# ADC_PWM_Board_-_Rev_A2.net
KiCad netlist of a schematic drawn in EAGLE
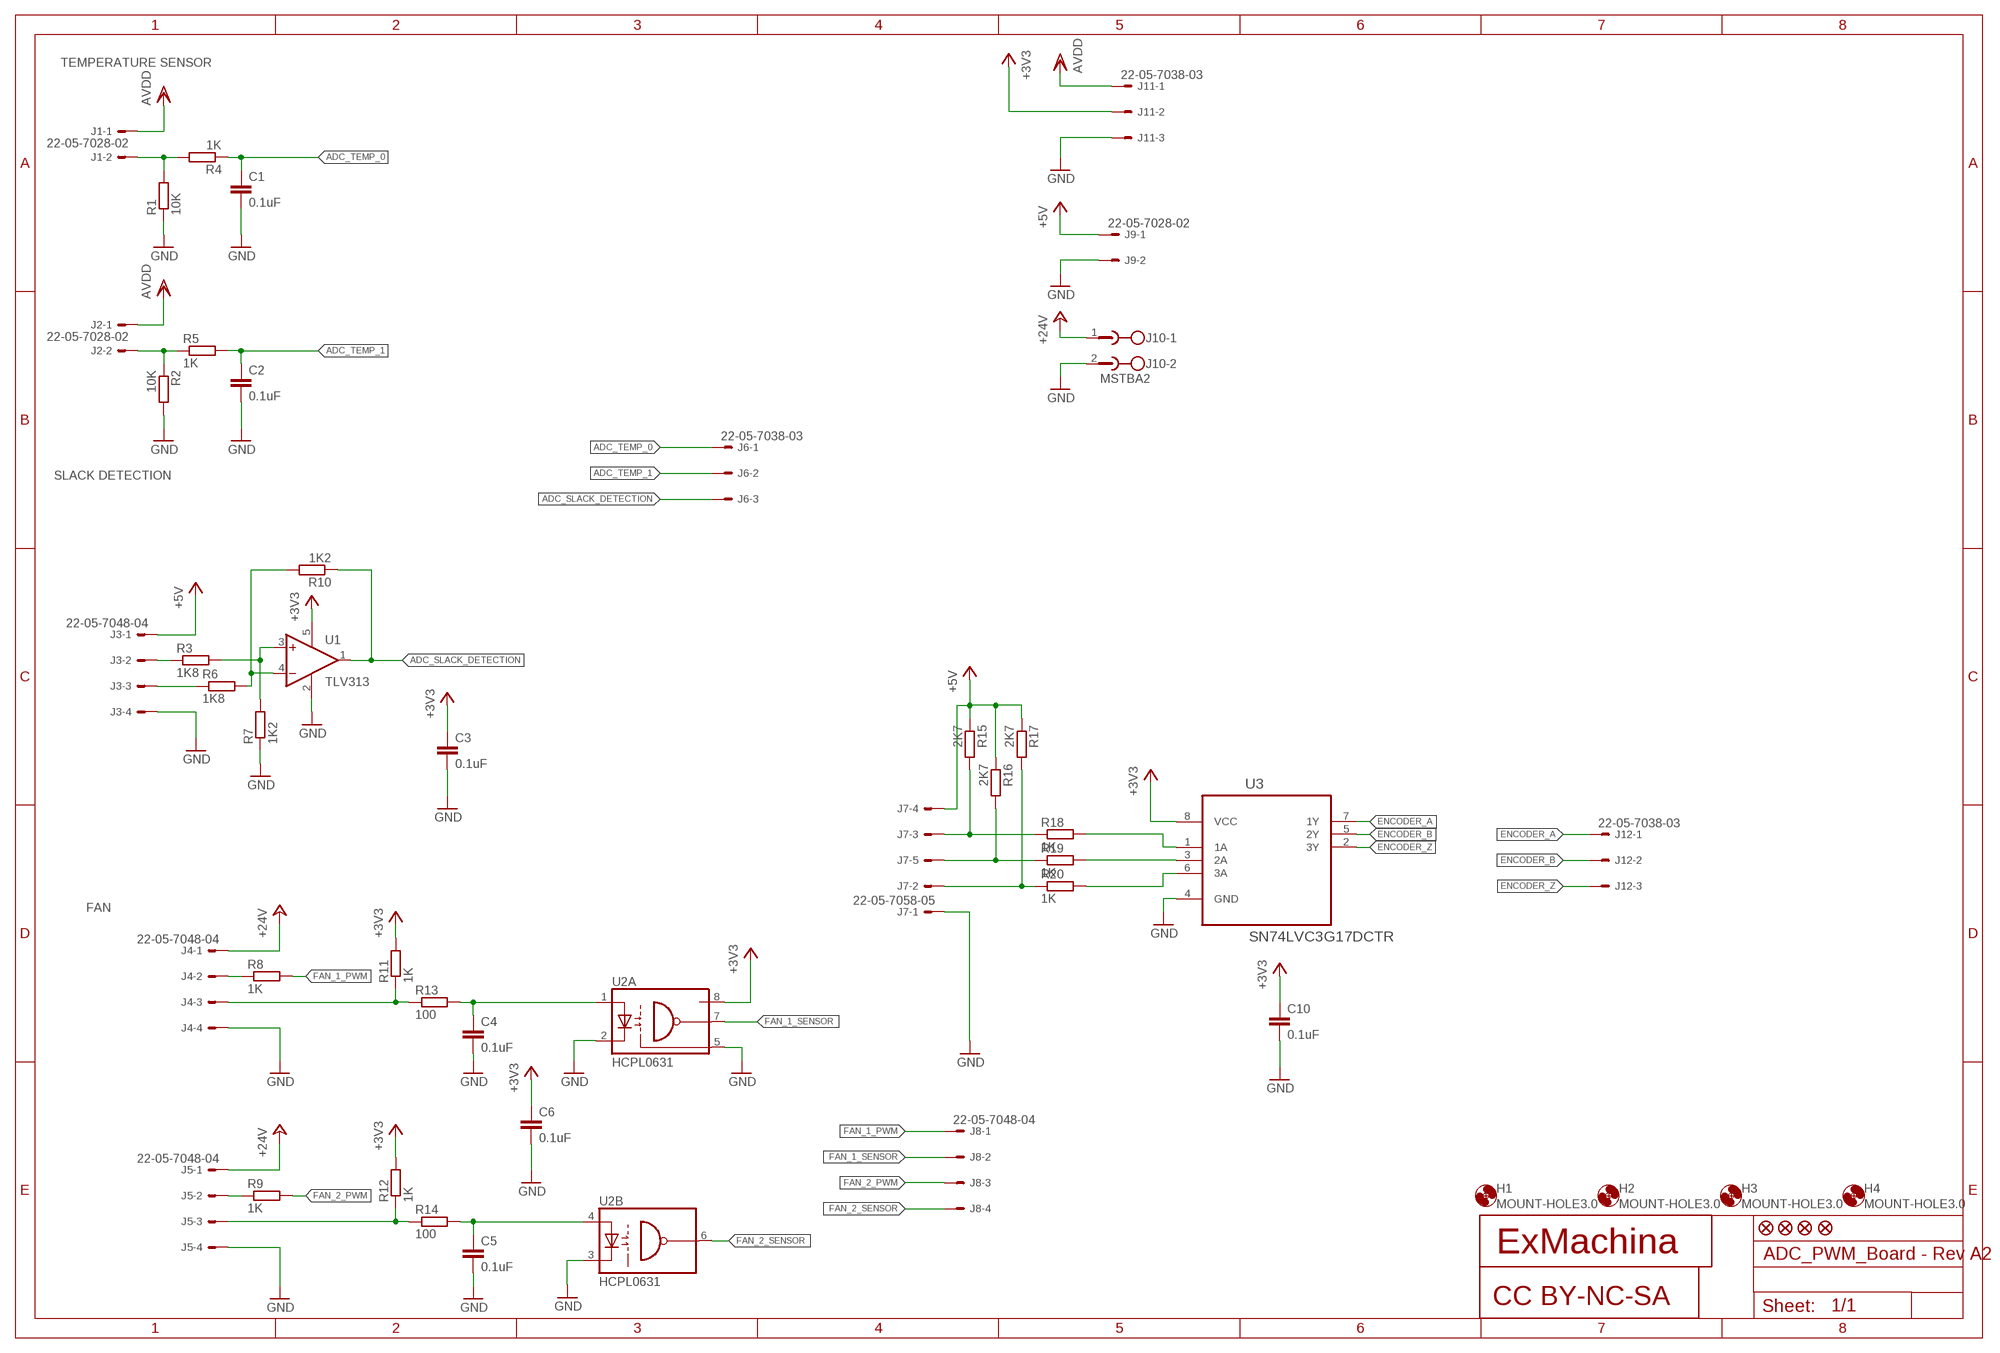
[diagram p0: schematic, sheet 1]

(export (version "E")
  (design (tool "Eeschema 10.0.6"))
  (components
    (comp (ref "C1")
      (value "0.1uF")
      (footprint "eagle-import:C0603")
      (fields (field (name "MPN") "MC0603B104K250CT"))
      (libsource (lib "eagle-import") (part "C-EUC0603"))
    )
    (comp (ref "C2")
      (value "0.1uF")
      (footprint "eagle-import:C0603")
      (fields (field (name "MPN") "MC0603B104K250CT"))
      (libsource (lib "eagle-import") (part "C-EUC0603"))
    )
    (comp (ref "C3")
      (value "0.1uF")
      (footprint "eagle-import:C0603")
      (fields (field (name "MPN") "MC0603B104K250CT"))
      (libsource (lib "eagle-import") (part "C-EUC0603"))
    )
    (comp (ref "C4")
      (value "0.1uF")
      (footprint "eagle-import:C0603")
      (fields (field (name "MPN") "MC0603B104K250CT"))
      (libsource (lib "eagle-import") (part "C-EUC0603"))
    )
    (comp (ref "C5")
      (value "0.1uF")
      (footprint "eagle-import:C0603")
      (fields (field (name "MPN") "MC0603B104K250CT"))
      (libsource (lib "eagle-import") (part "C-EUC0603"))
    )
    (comp (ref "C6")
      (value "0.1uF")
      (footprint "eagle-import:C0603")
      (fields (field (name "MPN") "MC0603B104K250CT"))
      (libsource (lib "eagle-import") (part "C-EUC0603"))
    )
    (comp (ref "C10")
      (value "0.1uF")
      (footprint "eagle-import:C0603")
      (fields (field (name "MPN") "MC0603B104K250CT"))
      (libsource (lib "eagle-import") (part "C-EUC0603"))
    )
    (comp (ref "CC1")
      (value "CC-BY-NC-SA")
      (footprint "eagle-import:CC-BY-NC-SA")
      (libsource (lib "eagle-import") (part "CC-BY-NC-SA"))
    )
    (comp (ref "H1")
      (value "MOUNT-HOLE3.0")
      (footprint "eagle-import:3,0")
      (libsource (lib "eagle-import") (part "MOUNT-HOLE3.0"))
    )
    (comp (ref "H2")
      (value "MOUNT-HOLE3.0")
      (footprint "eagle-import:3,0")
      (libsource (lib "eagle-import") (part "MOUNT-HOLE3.0"))
    )
    (comp (ref "H3")
      (value "MOUNT-HOLE3.0")
      (footprint "eagle-import:3,0")
      (libsource (lib "eagle-import") (part "MOUNT-HOLE3.0"))
    )
    (comp (ref "H4")
      (value "MOUNT-HOLE3.0")
      (footprint "eagle-import:3,0")
      (libsource (lib "eagle-import") (part "MOUNT-HOLE3.0"))
    )
    (comp (ref "J1")
      (value "22-05-7028-02")
      (footprint "eagle-import:7395-02")
      (fields (field (name "MPN") "22-05-7028") (field (name "OC_NEWARK") "25M1728"))
      (libsource (lib "eagle-import") (part "22-?-0205-7028"))
    )
    (comp (ref "J2")
      (value "22-05-7028-02")
      (footprint "eagle-import:7395-02")
      (fields (field (name "MPN") "22-05-7028") (field (name "OC_NEWARK") "25M1728"))
      (libsource (lib "eagle-import") (part "22-?-0205-7028"))
    )
    (comp (ref "J3")
      (value "22-05-7048-04")
      (footprint "eagle-import:7395-04")
      (fields (field (name "MPN") "22-05-7048") (field (name "OC_NEWARK") "26M6363"))
      (libsource (lib "eagle-import") (part "22-?-0405-7048"))
    )
    (comp (ref "J4")
      (value "22-05-7048-04")
      (footprint "eagle-import:7395-04")
      (fields (field (name "MPN") "22-05-7048") (field (name "OC_NEWARK") "26M6363"))
      (libsource (lib "eagle-import") (part "22-?-0405-7048"))
    )
    (comp (ref "J5")
      (value "22-05-7048-04")
      (footprint "eagle-import:7395-04")
      (fields (field (name "MPN") "22-05-7048") (field (name "OC_NEWARK") "26M6363"))
      (libsource (lib "eagle-import") (part "22-?-0405-7048"))
    )
    (comp (ref "J6")
      (value "22-05-7038-03")
      (footprint "eagle-import:7395-03")
      (fields (field (name "MPN") "22-05-7038") (field (name "OC_NEWARK") "26M6362"))
      (libsource (lib "eagle-import") (part "22-?-0305-7038"))
    )
    (comp (ref "J7")
      (value "22-05-7058-05")
      (footprint "eagle-import:7395-05")
      (fields
        (field (name "MF") "MOLEX")
        (field (name "MPN") "22-05-7058")
        (field (name "OC_NEWARK") "55H9619")
      )
      (libsource (lib "eagle-import") (part "22-?-0505-7058"))
    )
    (comp (ref "J8")
      (value "22-05-7048-04")
      (footprint "eagle-import:7395-04")
      (fields (field (name "MPN") "22-05-7048") (field (name "OC_NEWARK") "26M6363"))
      (libsource (lib "eagle-import") (part "22-?-0405-7048"))
    )
    (comp (ref "J9")
      (value "22-05-7028-02")
      (footprint "eagle-import:7395-02")
      (fields (field (name "MPN") "22-05-7028") (field (name "OC_NEWARK") "25M1728"))
      (libsource (lib "eagle-import") (part "22-?-0205-7028"))
    )
    (comp (ref "J10")
      (value "MSTBA2")
      (footprint "eagle-import:MSTBA2")
      (fields (field (name "MF") "FARNELL") (field (name "MPN") "1757242"))
      (libsource (lib "eagle-import") (part "MSTBA2"))
    )
    (comp (ref "J11")
      (value "22-05-7038-03")
      (footprint "eagle-import:7395-03")
      (fields (field (name "MPN") "22-05-7038") (field (name "OC_NEWARK") "26M6362"))
      (libsource (lib "eagle-import") (part "22-?-0305-7038"))
    )
    (comp (ref "J12")
      (value "22-05-7038-03")
      (footprint "eagle-import:7395-03")
      (fields (field (name "MPN") "22-05-7038") (field (name "OC_NEWARK") "26M6362"))
      (libsource (lib "eagle-import") (part "22-?-0305-7038"))
    )
    (comp (ref "JP1")
      (value "FIDUCIAL1X2")
      (footprint "eagle-import:FIDUCIAL-1X2")
      (libsource (lib "eagle-import") (part "FIDUCIAL1X2"))
    )
    (comp (ref "JP2")
      (value "FIDUCIAL1X2")
      (footprint "eagle-import:FIDUCIAL-1X2")
      (libsource (lib "eagle-import") (part "FIDUCIAL1X2"))
    )
    (comp (ref "JP3")
      (value "FIDUCIAL1X2")
      (footprint "eagle-import:FIDUCIAL-1X2")
      (libsource (lib "eagle-import") (part "FIDUCIAL1X2"))
    )
    (comp (ref "JP4")
      (value "FIDUCIAL1X2")
      (footprint "eagle-import:FIDUCIAL-1X2")
      (libsource (lib "eagle-import") (part "FIDUCIAL1X2"))
    )
    (comp (ref "R1")
      (value "10K")
      (footprint "eagle-import:R0603")
      (fields (field (name "MPN") "MCMR06X1002FTL"))
      (libsource (lib "eagle-import") (part "R-EU_R0603"))
    )
    (comp (ref "R2")
      (value "10K")
      (footprint "eagle-import:R0603")
      (fields (field (name "MPN") "MCMR06X1002FTL"))
      (libsource (lib "eagle-import") (part "R-EU_R0603"))
    )
    (comp (ref "R3")
      (value "1K8")
      (footprint "eagle-import:R0603")
      (fields (field (name "MPN") "MCMR06X1801FTL"))
      (libsource (lib "eagle-import") (part "R-EU_R0603"))
    )
    (comp (ref "R4")
      (value "1K")
      (footprint "eagle-import:R0603")
      (fields (field (name "MPN") "MCMR06X1001FTL"))
      (libsource (lib "eagle-import") (part "R-EU_R0603"))
    )
    (comp (ref "R5")
      (value "1K")
      (footprint "eagle-import:R0603")
      (fields (field (name "MPN") "MCMR06X1001FTL"))
      (libsource (lib "eagle-import") (part "R-EU_R0603"))
    )
    (comp (ref "R6")
      (value "1K8")
      (footprint "eagle-import:R0603")
      (fields (field (name "MPN") "MCMR06X1801FTL"))
      (libsource (lib "eagle-import") (part "R-EU_R0603"))
    )
    (comp (ref "R7")
      (value "1K2")
      (footprint "eagle-import:R0603")
      (fields (field (name "MPN") "MCMR06X1201FTL"))
      (libsource (lib "eagle-import") (part "R-EU_R0603"))
    )
    (comp (ref "R8")
      (value "1K")
      (footprint "eagle-import:R0603")
      (fields (field (name "MPN") "MCMR06X1001FTL"))
      (libsource (lib "eagle-import") (part "R-EU_R0603"))
    )
    (comp (ref "R9")
      (value "1K")
      (footprint "eagle-import:R0603")
      (fields (field (name "MPN") "MCMR06X1001FTL"))
      (libsource (lib "eagle-import") (part "R-EU_R0603"))
    )
    (comp (ref "R10")
      (value "1K2")
      (footprint "eagle-import:R0603")
      (fields (field (name "MPN") "MCMR06X1201FTL"))
      (libsource (lib "eagle-import") (part "R-EU_R0603"))
    )
    (comp (ref "R11")
      (value "1K")
      (footprint "eagle-import:R0603")
      (fields (field (name "MPN") "MCMR06X1001FTL"))
      (libsource (lib "eagle-import") (part "R-EU_R0603"))
    )
    (comp (ref "R12")
      (value "1K")
      (footprint "eagle-import:R0603")
      (fields (field (name "MPN") "MCMR06X1001FTL"))
      (libsource (lib "eagle-import") (part "R-EU_R0603"))
    )
    (comp (ref "R13")
      (value "100")
      (footprint "eagle-import:R0603")
      (fields (field (name "MPN") "MCMR06X1000FTL"))
      (libsource (lib "eagle-import") (part "R-EU_R0603"))
    )
    (comp (ref "R14")
      (value "100")
      (footprint "eagle-import:R0603")
      (fields (field (name "MPN") "MCMR06X1000FTL"))
      (libsource (lib "eagle-import") (part "R-EU_R0603"))
    )
    (comp (ref "R15")
      (value "2K7")
      (footprint "eagle-import:R0603")
      (fields (field (name "MPN") "MCMR06X4701FTL"))
      (libsource (lib "eagle-import") (part "R-EU_R0603"))
    )
    (comp (ref "R16")
      (value "2K7")
      (footprint "eagle-import:R0603")
      (fields (field (name "MPN") "MCMR06X4701FTL"))
      (libsource (lib "eagle-import") (part "R-EU_R0603"))
    )
    (comp (ref "R17")
      (value "2K7")
      (footprint "eagle-import:R0603")
      (fields (field (name "MPN") "MCMR06X4701FTL"))
      (libsource (lib "eagle-import") (part "R-EU_R0603"))
    )
    (comp (ref "R18")
      (value "1K")
      (footprint "eagle-import:R0603")
      (fields (field (name "MPN") "MCMR06X1000FTL"))
      (libsource (lib "eagle-import") (part "R-EU_R0603"))
    )
    (comp (ref "R19")
      (value "1K")
      (footprint "eagle-import:R0603")
      (fields (field (name "MPN") "MCMR06X1000FTL"))
      (libsource (lib "eagle-import") (part "R-EU_R0603"))
    )
    (comp (ref "R20")
      (value "1K")
      (footprint "eagle-import:R0603")
      (fields (field (name "MPN") "MCMR06X1000FTL"))
      (libsource (lib "eagle-import") (part "R-EU_R0603"))
    )
    (comp (ref "T1")
      (value "EXMACHINA-LOGO-NAME")
      (footprint "eagle-import:EXM-LOGO-BASELINE")
      (libsource (lib "eagle-import") (part "EXMACHINA-LOGO-NAME"))
    )
    (comp (ref "U1")
      (value "TLV313")
      (footprint "eagle-import:SOT23-DBV")
      (fields (field (name "MPN") "TLV313IDBVT"))
      (libsource (lib "eagle-import") (part "TLV313"))
    )
    (comp (ref "U2")
      (value "HCPL0631")
      (footprint "eagle-import:SOIC08")
      (fields (field (name "MPN") "HCPL-0631-500E") (field (name "OC_NEWARK") "52M7944"))
      (libsource (lib "eagle-import") (part "HCPL0631"))
    )
    (comp (ref "U3")
      (value "SN74LVC3G17DCTR")
      (footprint "eagle-import:SOP65P400X130-8N")
      (fields (field (name "MF") "TEXAS INSTRUMENTS"))
      (libsource (lib "eagle-import") (part "SN74LVC3G17DCTR"))
    )
  )
  (nets
    (net (code "1") (name "+3V3") (class "Default")
      (node (ref "C10") (pin "1") (pinfunction "1_1") (pintype "passive"))
      (node (ref "C3") (pin "1") (pinfunction "1_1") (pintype "passive"))
      (node (ref "C6") (pin "1") (pinfunction "1_1") (pintype "passive"))
      (node (ref "J11") (pin "2") (pinfunction "S_2") (pintype "passive"))
      (node (ref "R11") (pin "2") (pinfunction "2_2") (pintype "passive"))
      (node (ref "R12") (pin "2") (pinfunction "2_2") (pintype "passive"))
      (node (ref "U1") (pin "5") (pinfunction "V+_5") (pintype "power_in"))
      (node (ref "U2") (pin "8") (pinfunction "VCC_8") (pintype "power_in"))
      (node (ref "U3") (pin "8") (pinfunction "VCC_8") (pintype "power_in"))
    )
    (net (code "2") (name "+5V") (class "Default")
      (node (ref "J3") (pin "1") (pinfunction "S_1") (pintype "passive"))
      (node (ref "J7") (pin "4") (pinfunction "S_4") (pintype "passive"))
      (node (ref "J9") (pin "1") (pinfunction "S_1") (pintype "passive"))
      (node (ref "R15") (pin "1") (pinfunction "1_1") (pintype "passive"))
      (node (ref "R16") (pin "1") (pinfunction "1_1") (pintype "passive"))
      (node (ref "R17") (pin "1") (pinfunction "1_1") (pintype "passive"))
    )
    (net (code "3") (name "+24V") (class "Default")
      (node (ref "J10") (pin "1") (pinfunction "1_1") (pintype "passive"))
      (node (ref "J4") (pin "1") (pinfunction "S_1") (pintype "passive"))
      (node (ref "J5") (pin "1") (pinfunction "S_1") (pintype "passive"))
    )
    (net (code "4") (name "ADC_SLACK_DETECTION") (class "Default")
      (node (ref "J6") (pin "3") (pinfunction "S_3") (pintype "passive"))
      (node (ref "R10") (pin "1") (pinfunction "1_1") (pintype "passive"))
      (node (ref "U1") (pin "1") (pinfunction "OUT_1") (pintype "output"))
    )
    (net (code "5") (name "ADC_TEMP_0") (class "Default")
      (node (ref "C1") (pin "1") (pinfunction "1_1") (pintype "passive"))
      (node (ref "J6") (pin "1") (pinfunction "S_1") (pintype "passive"))
      (node (ref "R4") (pin "1") (pinfunction "1_1") (pintype "passive"))
    )
    (net (code "6") (name "ADC_TEMP_1") (class "Default")
      (node (ref "C2") (pin "1") (pinfunction "1_1") (pintype "passive"))
      (node (ref "J6") (pin "2") (pinfunction "S_2") (pintype "passive"))
      (node (ref "R5") (pin "2") (pinfunction "2_2") (pintype "passive"))
    )
    (net (code "7") (name "AVDD") (class "Default")
      (node (ref "J1") (pin "1") (pinfunction "S_1") (pintype "passive"))
      (node (ref "J11") (pin "1") (pinfunction "S_1") (pintype "passive"))
      (node (ref "J2") (pin "1") (pinfunction "S_1") (pintype "passive"))
    )
    (net (code "8") (name "ENCODER_A") (class "Default")
      (node (ref "J12") (pin "1") (pinfunction "S_1") (pintype "passive"))
      (node (ref "U3") (pin "7") (pinfunction "1Y_7") (pintype "output"))
    )
    (net (code "9") (name "ENCODER_B") (class "Default")
      (node (ref "J12") (pin "2") (pinfunction "S_2") (pintype "passive"))
      (node (ref "U3") (pin "5") (pinfunction "2Y_5") (pintype "output"))
    )
    (net (code "10") (name "ENCODER_Z") (class "Default")
      (node (ref "J12") (pin "3") (pinfunction "S_3") (pintype "passive"))
      (node (ref "U3") (pin "2") (pinfunction "3Y_2") (pintype "output"))
    )
    (net (code "11") (name "FAN_1_PWM") (class "Default")
      (node (ref "J8") (pin "1") (pinfunction "S_1") (pintype "passive"))
      (node (ref "R8") (pin "2") (pinfunction "2_2") (pintype "passive"))
    )
    (net (code "12") (name "FAN_1_SENSOR") (class "Default")
      (node (ref "J8") (pin "2") (pinfunction "S_2") (pintype "passive"))
      (node (ref "U2") (pin "7") (pinfunction "VO_7") (pintype "passive"))
    )
    (net (code "13") (name "FAN_2_PWM") (class "Default")
      (node (ref "J8") (pin "3") (pinfunction "S_3") (pintype "passive"))
      (node (ref "R9") (pin "2") (pinfunction "2_2") (pintype "passive"))
    )
    (net (code "14") (name "FAN_2_SENSOR") (class "Default")
      (node (ref "J8") (pin "4") (pinfunction "S_4") (pintype "passive"))
      (node (ref "U2") (pin "6") (pinfunction "VO2_6") (pintype "passive"))
    )
    (net (code "15") (name "GND") (class "Default")
      (node (ref "C1") (pin "2") (pinfunction "2_2") (pintype "passive"))
      (node (ref "C10") (pin "2") (pinfunction "2_2") (pintype "passive"))
      (node (ref "C2") (pin "2") (pinfunction "2_2") (pintype "passive"))
      (node (ref "C3") (pin "2") (pinfunction "2_2") (pintype "passive"))
      (node (ref "C4") (pin "2") (pinfunction "2_2") (pintype "passive"))
      (node (ref "C5") (pin "2") (pinfunction "2_2") (pintype "passive"))
      (node (ref "C6") (pin "2") (pinfunction "2_2") (pintype "passive"))
      (node (ref "J10") (pin "2") (pinfunction "1_2") (pintype "passive"))
      (node (ref "J11") (pin "3") (pinfunction "S_3") (pintype "passive"))
      (node (ref "J3") (pin "4") (pinfunction "S_4") (pintype "passive"))
      (node (ref "J4") (pin "4") (pinfunction "S_4") (pintype "passive"))
      (node (ref "J5") (pin "4") (pinfunction "S_4") (pintype "passive"))
      (node (ref "J7") (pin "1") (pinfunction "S_1") (pintype "passive"))
      (node (ref "J9") (pin "2") (pinfunction "S_2") (pintype "passive"))
      (node (ref "R1") (pin "1") (pinfunction "1_1") (pintype "passive"))
      (node (ref "R2") (pin "2") (pinfunction "2_2") (pintype "passive"))
      (node (ref "R7") (pin "1") (pinfunction "1_1") (pintype "passive"))
      (node (ref "U1") (pin "2") (pinfunction "V-_2") (pintype "power_in"))
      (node (ref "U2") (pin "2") (pinfunction "C1_2") (pintype "passive"))
      (node (ref "U2") (pin "3") (pinfunction "C2_3") (pintype "passive"))
      (node (ref "U2") (pin "5") (pinfunction "GND_5") (pintype "passive"))
      (node (ref "U3") (pin "4") (pinfunction "GND_4") (pintype "passive"))
    )
    (net (code "16") (name "Net-(J1B-S)") (class "Default")
      (node (ref "J1") (pin "2") (pinfunction "S_2") (pintype "passive"))
      (node (ref "R1") (pin "2") (pinfunction "2_2") (pintype "passive"))
      (node (ref "R4") (pin "2") (pinfunction "2_2") (pintype "passive"))
    )
    (net (code "17") (name "Net-(J2B-S)") (class "Default")
      (node (ref "J2") (pin "2") (pinfunction "S_2") (pintype "passive"))
      (node (ref "R2") (pin "1") (pinfunction "1_1") (pintype "passive"))
      (node (ref "R5") (pin "1") (pinfunction "1_1") (pintype "passive"))
    )
    (net (code "18") (name "Net-(J3B-S)") (class "Default")
      (node (ref "J3") (pin "2") (pinfunction "S_2") (pintype "passive"))
      (node (ref "R3") (pin "1") (pinfunction "1_1") (pintype "passive"))
    )
    (net (code "19") (name "Net-(J3C-S)") (class "Default")
      (node (ref "J3") (pin "3") (pinfunction "S_3") (pintype "passive"))
      (node (ref "R6") (pin "1") (pinfunction "1_1") (pintype "passive"))
    )
    (net (code "20") (name "Net-(J4B-S)") (class "Default")
      (node (ref "J4") (pin "2") (pinfunction "S_2") (pintype "passive"))
      (node (ref "R8") (pin "1") (pinfunction "1_1") (pintype "passive"))
    )
    (net (code "21") (name "Net-(J4C-S)") (class "Default")
      (node (ref "J4") (pin "3") (pinfunction "S_3") (pintype "passive"))
      (node (ref "R11") (pin "1") (pinfunction "1_1") (pintype "passive"))
      (node (ref "R13") (pin "1") (pinfunction "1_1") (pintype "passive"))
    )
    (net (code "22") (name "Net-(J5B-S)") (class "Default")
      (node (ref "J5") (pin "2") (pinfunction "S_2") (pintype "passive"))
      (node (ref "R9") (pin "1") (pinfunction "1_1") (pintype "passive"))
    )
    (net (code "23") (name "Net-(J5C-S)") (class "Default")
      (node (ref "J5") (pin "3") (pinfunction "S_3") (pintype "passive"))
      (node (ref "R12") (pin "1") (pinfunction "1_1") (pintype "passive"))
      (node (ref "R14") (pin "1") (pinfunction "1_1") (pintype "passive"))
    )
    (net (code "24") (name "Net-(J7B-S)") (class "Default")
      (node (ref "J7") (pin "2") (pinfunction "S_2") (pintype "passive"))
      (node (ref "R17") (pin "2") (pinfunction "2_2") (pintype "passive"))
      (node (ref "R20") (pin "1") (pinfunction "1_1") (pintype "passive"))
    )
    (net (code "25") (name "Net-(J7C-S)") (class "Default")
      (node (ref "J7") (pin "3") (pinfunction "S_3") (pintype "passive"))
      (node (ref "R15") (pin "2") (pinfunction "2_2") (pintype "passive"))
      (node (ref "R18") (pin "1") (pinfunction "1_1") (pintype "passive"))
    )
    (net (code "26") (name "Net-(J7E-S)") (class "Default")
      (node (ref "J7") (pin "5") (pinfunction "S_5") (pintype "passive"))
      (node (ref "R16") (pin "2") (pinfunction "2_2") (pintype "passive"))
      (node (ref "R19") (pin "1") (pinfunction "1_1") (pintype "passive"))
    )
    (net (code "27") (name "Net-(U1-+IN)") (class "Default")
      (node (ref "R3") (pin "2") (pinfunction "2_2") (pintype "passive"))
      (node (ref "R7") (pin "2") (pinfunction "2_2") (pintype "passive"))
      (node (ref "U1") (pin "3") (pinfunction "+IN_3") (pintype "input"))
    )
    (net (code "28") (name "Net-(U1--IN)") (class "Default")
      (node (ref "R10") (pin "2") (pinfunction "2_2") (pintype "passive"))
      (node (ref "R6") (pin "2") (pinfunction "2_2") (pintype "passive"))
      (node (ref "U1") (pin "4") (pinfunction "-IN_4") (pintype "input"))
    )
    (net (code "29") (name "Net-(U2A-A1)") (class "Default")
      (node (ref "C4") (pin "1") (pinfunction "1_1") (pintype "passive"))
      (node (ref "R13") (pin "2") (pinfunction "2_2") (pintype "passive"))
      (node (ref "U2") (pin "1") (pinfunction "A1_1") (pintype "passive"))
    )
    (net (code "30") (name "Net-(U2B-A2)") (class "Default")
      (node (ref "C5") (pin "1") (pinfunction "1_1") (pintype "passive"))
      (node (ref "R14") (pin "2") (pinfunction "2_2") (pintype "passive"))
      (node (ref "U2") (pin "4") (pinfunction "A2_4") (pintype "passive"))
    )
    (net (code "31") (name "Net-(U3-1A)") (class "Default")
      (node (ref "R18") (pin "2") (pinfunction "2_2") (pintype "passive"))
      (node (ref "U3") (pin "1") (pinfunction "1A_1") (pintype "input"))
    )
    (net (code "32") (name "Net-(U3-2A)") (class "Default")
      (node (ref "R19") (pin "2") (pinfunction "2_2") (pintype "passive"))
      (node (ref "U3") (pin "3") (pinfunction "2A_3") (pintype "input"))
    )
    (net (code "33") (name "Net-(U3-3A)") (class "Default")
      (node (ref "R20") (pin "2") (pinfunction "2_2") (pintype "passive"))
      (node (ref "U3") (pin "6") (pinfunction "3A_6") (pintype "input"))
    )
  )
)
